# power_supply.net
KiCad netlist of a schematic drawn in Altium Designer
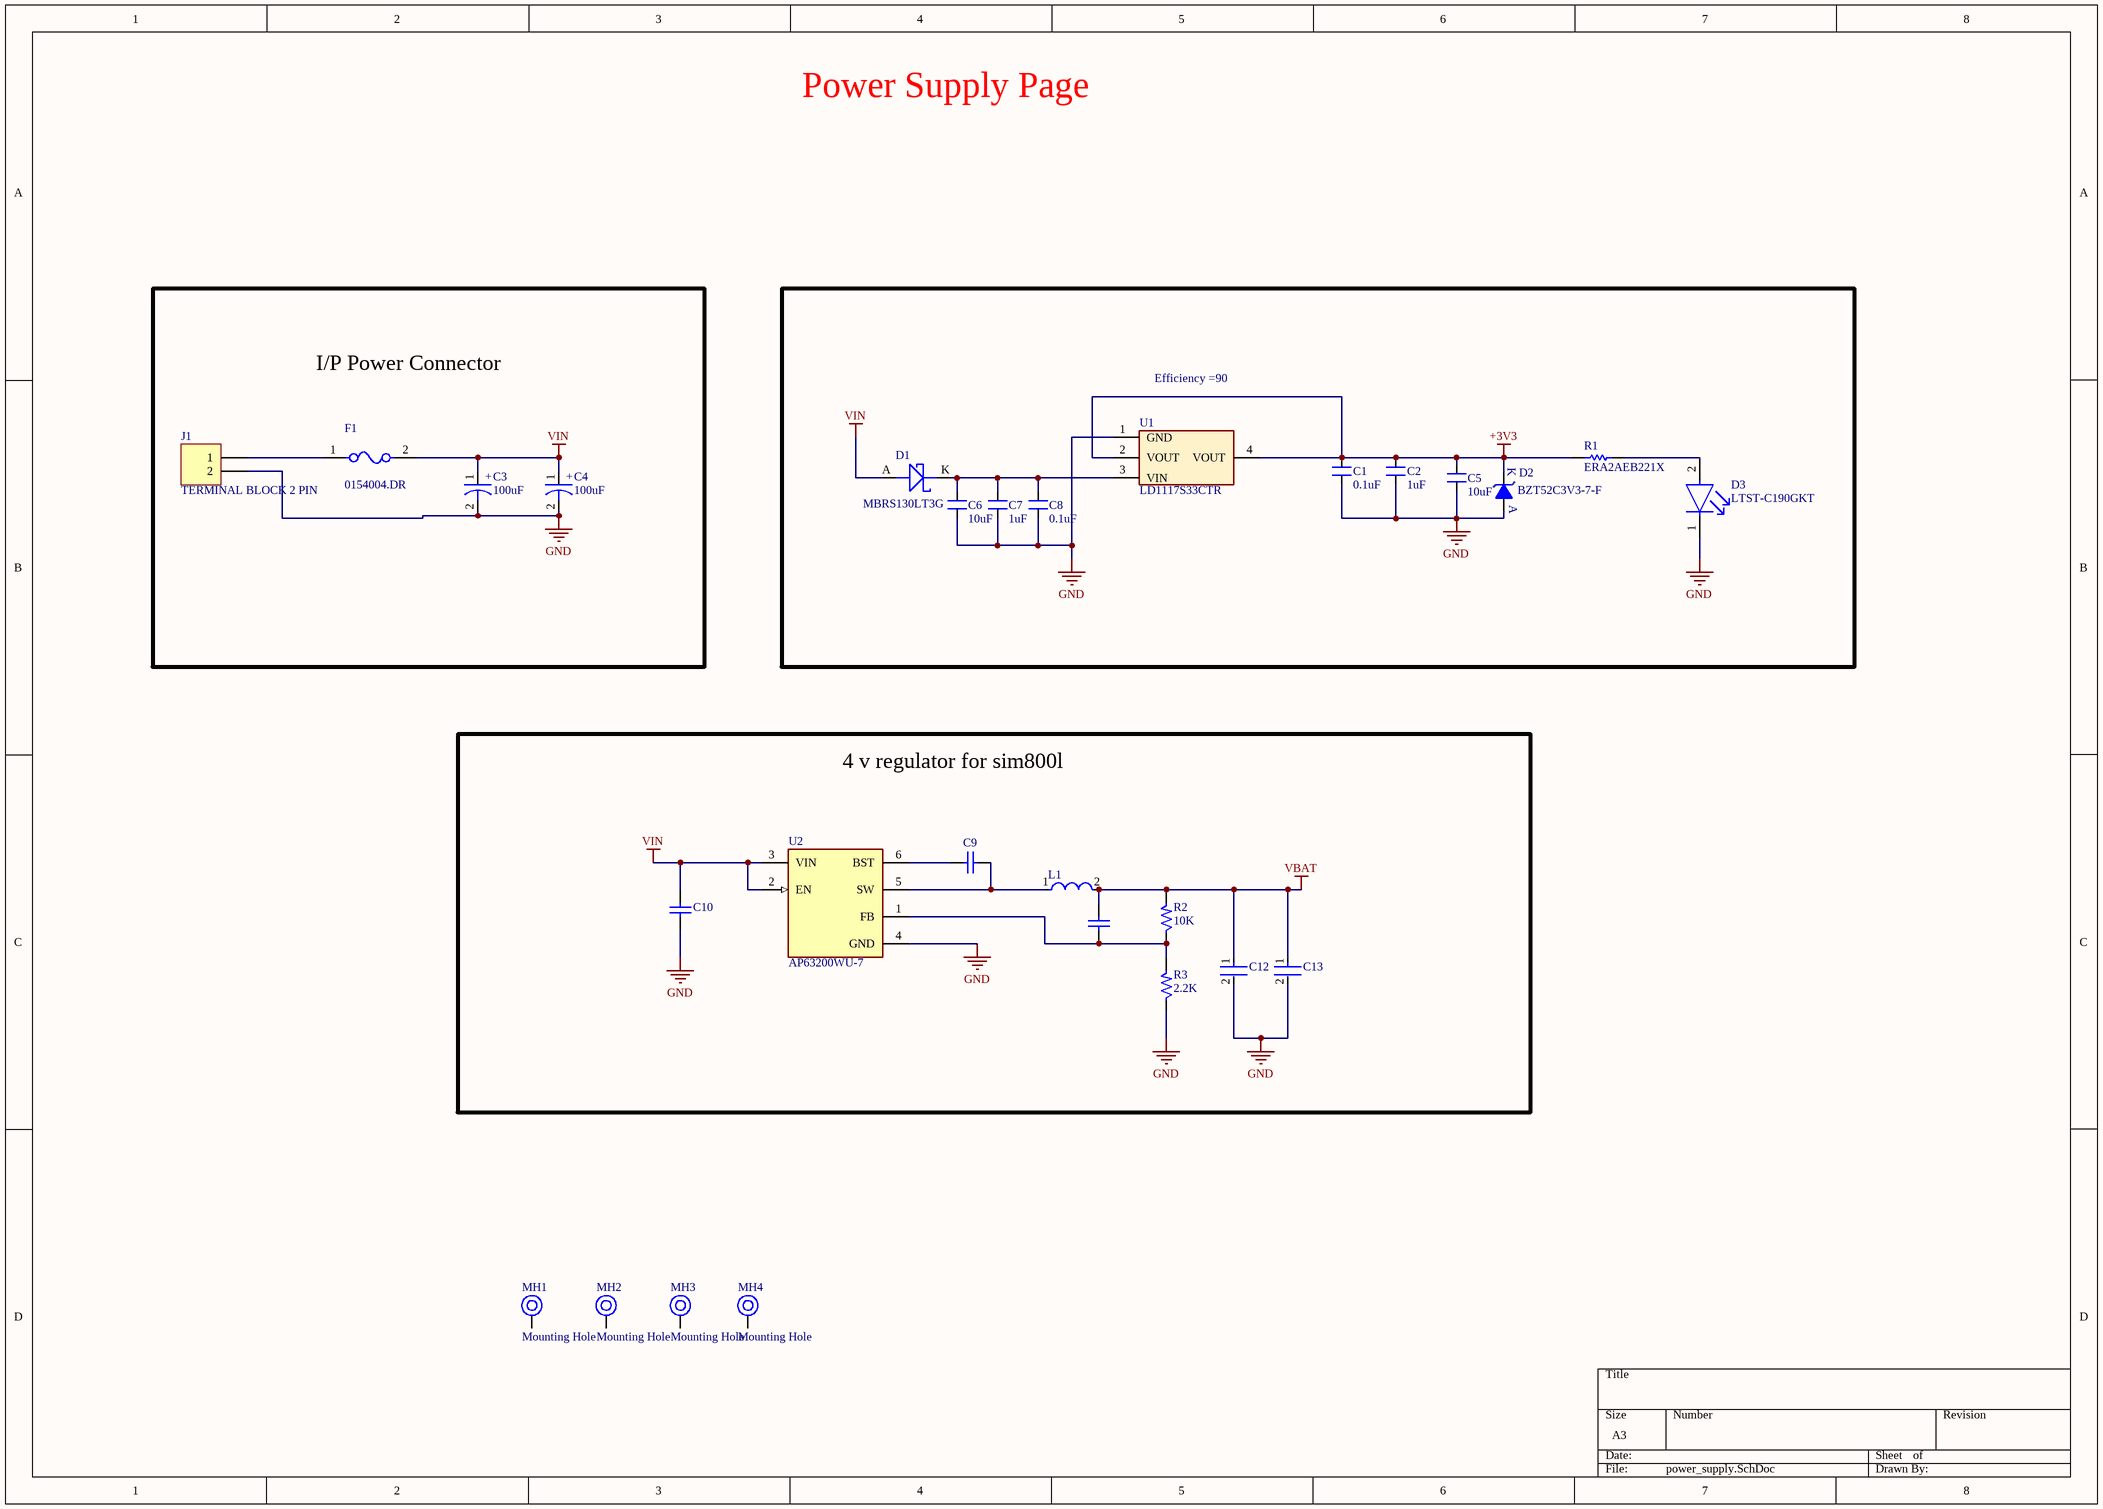
[diagram p0: power_supply.SchDoc]

(export (version "E")
  (design (tool "Eeschema 10.0.6"))
  (components
    (comp (ref "C1")
      (value "0.1uF")
      (footprint "CAP_0805")
      (description "0.1µF ±10% 50V Ceramic Capacitor X7R 0805 (2012 Metric)")
      (fields
        (field (name "MANUFACTURER") "Samsung")
        (field (name "MANUFACTURER PART NUMBER") "CL21B104KBCNNNC")
      )
      (libsource (lib "ESTEEMPCBLIB") (part "CAP_0.1uF-50V-10%-0805"))
    )
    (comp (ref "C2")
      (value "1uF")
      (footprint "CAP_0805")
      (description "1µF ±5% 50V Ceramic Capacitor X7R 0805 (2012 Metric)")
      (fields
        (field (name "MANUFACTURER") "Samsung")
        (field (name "MANUFACTURER PART NUMBER") "CC0805JKX7R9BB105")
      )
      (libsource (lib "ESTEEMPCBLIB") (part "CAP_1uF-50V-5%-0805"))
    )
    (comp (ref "C3")
      (value "100uF")
      (footprint "ACAP_P305_D393_H393_RAD")
      (description "100µF 50V Aluminum Polymer Capacitor Radial, Can - SMD 28mOhm 4000 Hrs @ 125°C")
      (fields
        (field (name "MANUFACTURER") "Nichicon")
        (field (name "MANUFACTURER PART NUMBER") "GYA1H101MCQ1GS")
      )
      (libsource (lib "ESTEEMPCBLIB") (part "CAP-P_100uF-50V-20%-RAD"))
    )
    (comp (ref "C4")
      (value "100uF")
      (footprint "ACAP_P305_D393_H393_RAD")
      (description "100µF 50V Aluminum Polymer Capacitor Radial, Can - SMD 28mOhm 4000 Hrs @ 125°C")
      (fields
        (field (name "MANUFACTURER") "Nichicon")
        (field (name "MANUFACTURER PART NUMBER") "GYA1H101MCQ1GS")
      )
      (libsource (lib "ESTEEMPCBLIB") (part "CAP-P_100uF-50V-20%-RAD"))
    )
    (comp (ref "C5")
      (value "10uF")
      (footprint "CAP_1206")
      (description "10µF ±10% 50V Ceramic Capacitor X7R 1206 (3216 Metric)")
      (fields
        (field (name "MANUFACTURER") "KEMET")
        (field (name "MANUFACTURER PART NUMBER") "CL31B106KBHNNNE")
      )
      (libsource (lib "ESTEEMPCBLIB") (part "CAP_10uF-50V-10%-1206"))
    )
    (comp (ref "C6")
      (value "10uF")
      (footprint "CAP_1206")
      (description "10µF ±10% 50V Ceramic Capacitor X7R 1206 (3216 Metric)")
      (fields
        (field (name "MANUFACTURER") "KEMET")
        (field (name "MANUFACTURER PART NUMBER") "CL31B106KBHNNNE")
      )
      (libsource (lib "ESTEEMPCBLIB") (part "CAP_10uF-50V-10%-1206"))
    )
    (comp (ref "C7")
      (value "1uF")
      (footprint "CAP_0805")
      (description "1µF ±5% 50V Ceramic Capacitor X7R 0805 (2012 Metric)")
      (fields
        (field (name "MANUFACTURER") "Samsung")
        (field (name "MANUFACTURER PART NUMBER") "CC0805JKX7R9BB105")
      )
      (libsource (lib "ESTEEMPCBLIB") (part "CAP_1uF-50V-5%-0805"))
    )
    (comp (ref "C8")
      (value "0.1uF")
      (footprint "CAP_0805")
      (description "0.1µF ±10% 50V Ceramic Capacitor X7R 0805 (2012 Metric)")
      (fields
        (field (name "MANUFACTURER") "Samsung")
        (field (name "MANUFACTURER PART NUMBER") "CL21B104KBCNNNC")
      )
      (libsource (lib "ESTEEMPCBLIB") (part "CAP_0.1uF-50V-10%-0805"))
    )
    (comp (ref "C9")
      (value "04026D104KAT2A")
      (footprint "CAPC1005X56X25LL10T15")
      (fields (field (name "MANUFACTURER") "AVX Interconnect / Elco"))
      (libsource (lib "Altium Content Vault") (part "CAP"))
    )
    (comp (ref "C10")
      (value "AMK105CBJ106MV-F")
      (footprint "CAPC0402(1005)60_N")
      (description "None")
      (fields (field (name "TOLERANCE") "20%"))
      (libsource (lib "Altium Content Vault") (part "CAP"))
    )
    (comp (ref "C11")
      (value "GRM1555C1H101JA01D")
      (footprint "CAPC1005X55X25ML05T10")
      (fields (field (name "MANUFACTURER") "Murata"))
      (libsource (lib "Altium Content Vault") (part "CAP"))
    )
    (comp (ref "C12")
      (value "GRM21BR60J226ME39L")
      (footprint "FP-GRM21B-0_15-IPC_B")
      (description "Chip Multilayer Ceramic Capacitors for General Purpose, 0805, 22uF, X5R, 15%, 20%, 6.3V")
      (fields (field (name "VOLTAGE") "6.3V") (field (name "TOLERANCE") "20%"))
      (libsource (lib "Altium Content Vault") (part "b4654b650e69147ec39a6b967a45e02"))
    )
    (comp (ref "C13")
      (value "GRM21BR60J226ME39L")
      (footprint "FP-GRM21B-0_15-IPC_B")
      (description "Chip Multilayer Ceramic Capacitors for General Purpose, 0805, 22uF, X5R, 15%, 20%, 6.3V")
      (fields (field (name "VOLTAGE") "6.3V") (field (name "TOLERANCE") "20%"))
      (libsource (lib "Altium Content Vault") (part "b4654b650e69147ec39a6b967a45e02"))
    )
    (comp (ref "D1")
      (value "MBRS130LT3G")
      (footprint "DIO_SMB_DO-214AA")
      (description "Diode Schottky 30V 2A Surface Mount SMB")
      (fields (field (name "MANUFACTURER") "ON Semiconductor"))
      (libsource (lib "ESTEEMPCBLIB") (part "DIO-S_445mV-30V-2A-SMB"))
    )
    (comp (ref "D2")
      (value "BZT52C3V3-7-F")
      (footprint "DIO_SOD-123")
      (description "Zener Diode 3.3V 500mW ±6% Surface Mount SOD-123")
      (fields (field (name "MANUFACTURER") "Diodes Incorporated"))
      (libsource (lib "ESTEEMPCBLIB") (part "DIO-Z_3.3V-500mW-SOD123"))
    )
    (comp (ref "D3")
      (value "LTST-C190GKT")
      (footprint "FP-LTST-C190GKT-MFG")
      (description "LED GREEN CLEAR CHIP SMD")
      (fields (field (name "VOLTAGE") "2V"))
      (libsource (lib "Altium Content Vault") (part "8706943c75ba83719d021d2fdc84c58"))
    )
    (comp (ref "F1")
      (value "0154004.DR")
      (footprint "FP-0154-MFG")
      (description "FUSE BRD MNT 4A 125VAC/VDC 2SMD")
      (fields
        (field (name "MANUFACTURER") "Littelfuse")
        (field (name "OCTOPART") "https://octopart.com/0154004.dr-littelfuse-565861")
      )
      (libsource (lib "Altium Content Vault") (part "5bcf9b9f640e542cf0359d10258e979"))
    )
    (comp (ref "J1")
      (value "TERMINAL BLOCK 2 PIN")
      (footprint "CON2_P196_1729128_TH_ST")
      (description "2 Pins, 1 Row 5mm Pitch, straight Connector, male")
      (fields
        (field (name "MANUFACTURER") "Phoenix Contact")
        (field (name "MANUFACTURER PART NUMBER") "MKDSN1,5/2")
      )
      (libsource (lib "ESTEEMPCBLIB") (part "CON-TB_2X1-196-ST-TH"))
    )
    (comp (ref "L1")
      (value "MLZ1005M2R2WT000")
      (footprint "FP-MLZ1005-IPC_B")
      (description "Shielded Multilayer Inductor 2.2uH ±20% 350mA 715mΩ SMD 0402")
      (fields (field (name "TOLERANCE") "20%"))
      (libsource (lib "Altium Content Vault") (part "725321dda6339637d4d059423bc1c3c"))
    )
    (comp (ref "MH1")
      (value "Mounting Hole")
      (footprint "MOUNTING")
      (fields (field (name "MANUFACTURER PART NUMBER") "NA"))
      (libsource (lib "ESTEEMPCBLIB") (part "MH_3.5H_6D"))
    )
    (comp (ref "MH2")
      (value "Mounting Hole")
      (footprint "MOUNTING")
      (fields (field (name "MANUFACTURER PART NUMBER") "NA"))
      (libsource (lib "ESTEEMPCBLIB") (part "MH_3.5H_6D"))
    )
    (comp (ref "MH3")
      (value "Mounting Hole")
      (footprint "MOUNTING")
      (fields (field (name "MANUFACTURER PART NUMBER") "NA"))
      (libsource (lib "ESTEEMPCBLIB") (part "MH_3.5H_6D"))
    )
    (comp (ref "MH4")
      (value "Mounting Hole")
      (footprint "MOUNTING")
      (fields (field (name "MANUFACTURER PART NUMBER") "NA"))
      (libsource (lib "ESTEEMPCBLIB") (part "MH_3.5H_6D"))
    )
    (comp (ref "R1")
      (value "ERA2AEB221X")
      (footprint "RESC1005X40X25LL10T10")
      (fields (field (name "MANUFACTURER") "Panasonic"))
      (libsource (lib "Altium Content Vault") (part "RES"))
    )
    (comp (ref "R2")
      (value "10K")
      (footprint "RES_0603")
      (description "10 kOhms ±1% 0.1W, 1/10W Chip Resistor 0603 (1608 Metric) Automotive AEC-Q200 Thick Film")
      (fields (field (name "MANUFACTURER") "Walsin") (field (name "MANUFACTURER PART NUMBER") "WR06X1002FTL"))
      (libsource (lib "ESTEEMPCBLIB") (part "RES_10K-0.1W-1%-0603"))
    )
    (comp (ref "R3")
      (value "2.2K")
      (footprint "RES_0805")
      (description "2.2 kOhms ±1% 0.125W, 1/8W Chip Resistor 0805 (2012 Metric) Thick Film")
      (fields
        (field (name "MANUFACTURER") "Stackpole Electronics")
        (field (name "MANUFACTURER PART NUMBER") "CRG0805F2K2")
      )
      (libsource (lib "ESTEEMPCBLIB") (part "RES_2.2K-0.125W-1%-0805"))
    )
    (comp (ref "U1")
      (value "LD1117S33CTR")
      (footprint "SOT223_3")
      (description "Linear Voltage Regulator IC 1 Output 800mA SOT-223")
      (fields (field (name "MANUFACTURER") "STMicroelectronics"))
      (libsource (lib "ESTEEMPCBLIB") (part "REG_15V-3.3V-0.9A-12W-SOT223"))
    )
    (comp (ref "U2")
      (value "AP63200WU-7")
      (footprint "FP-TSOT26-MFG")
      (description "IC REG BUCK ADJUSTABLE 2A TSOT26")
      (fields
        (field (name "OCTOPART") "https://octopart.com/ap63200wu-7-diodes+inc.-98099548")
        (field (name "MANUFACTURER") "Diodes Inc.")
      )
      (libsource (lib "Altium Content Vault") (part "2ae3aed49e7ee94ca813948749813a1"))
    )
  )
  (nets
    (net (code "1") (name "+3V3") (class "Default")
      (node (ref "C1") (pin "2") (pinfunction "2_2") (pintype "passive"))
      (node (ref "C2") (pin "2") (pinfunction "2_2") (pintype "passive"))
      (node (ref "C5") (pin "2") (pinfunction "2_2") (pintype "passive"))
      (node (ref "D2") (pin "K") (pinfunction "K_K") (pintype "passive"))
      (node (ref "R1") (pin "1") (pinfunction "1_1") (pintype "passive"))
      (node (ref "U1") (pin "2") (pinfunction "VOUT_2") (pintype "passive"))
      (node (ref "U1") (pin "4") (pinfunction "VOUT_4") (pintype "passive"))
    )
    (net (code "2") (name "GND") (class "Default")
      (node (ref "C1") (pin "1") (pinfunction "1_1") (pintype "passive"))
      (node (ref "C10") (pin "1") (pinfunction "1_1") (pintype "passive"))
      (node (ref "C12") (pin "2") (pinfunction "2_2") (pintype "passive"))
      (node (ref "C13") (pin "2") (pinfunction "2_2") (pintype "passive"))
      (node (ref "C2") (pin "1") (pinfunction "1_1") (pintype "passive"))
      (node (ref "C3") (pin "2") (pinfunction "2_2") (pintype "passive"))
      (node (ref "C4") (pin "2") (pinfunction "2_2") (pintype "passive"))
      (node (ref "C5") (pin "1") (pinfunction "1_1") (pintype "passive"))
      (node (ref "C6") (pin "1") (pinfunction "1_1") (pintype "passive"))
      (node (ref "C7") (pin "1") (pinfunction "1_1") (pintype "passive"))
      (node (ref "C8") (pin "1") (pinfunction "1_1") (pintype "passive"))
      (node (ref "D2") (pin "A") (pinfunction "A_A") (pintype "passive"))
      (node (ref "D3") (pin "1") (pinfunction "C_1") (pintype "passive"))
      (node (ref "J1") (pin "2") (pinfunction "2_2") (pintype "passive"))
      (node (ref "R3") (pin "1") (pinfunction "1_1") (pintype "passive"))
      (node (ref "U1") (pin "1") (pinfunction "GND_1") (pintype "passive"))
      (node (ref "U2") (pin "4") (pinfunction "GND_4") (pintype "power_in"))
    )
    (net (code "3") (name "Net-(D3-A)") (class "Default")
      (node (ref "D3") (pin "2") (pinfunction "A_2") (pintype "passive"))
      (node (ref "R1") (pin "2") (pinfunction "2_2") (pintype "passive"))
    )
    (net (code "4") (name "Net-(F1-Pad1)") (class "Default")
      (node (ref "F1") (pin "1") (pinfunction "1_1") (pintype "passive"))
      (node (ref "J1") (pin "1") (pinfunction "1_1") (pintype "passive"))
    )
    (net (code "5") (name "Net-(U1-VIN)") (class "Default")
      (node (ref "C6") (pin "2") (pinfunction "2_2") (pintype "passive"))
      (node (ref "C7") (pin "2") (pinfunction "2_2") (pintype "passive"))
      (node (ref "C8") (pin "2") (pinfunction "2_2") (pintype "passive"))
      (node (ref "D1") (pin "K") (pinfunction "K_K") (pintype "passive"))
      (node (ref "U1") (pin "3") (pinfunction "VIN_3") (pintype "passive"))
    )
    (net (code "6") (name "Net-(U2-BST)") (class "Default")
      (node (ref "C9") (pin "1") (pinfunction "1_1") (pintype "passive"))
      (node (ref "U2") (pin "6") (pinfunction "BST_6") (pintype "passive"))
    )
    (net (code "7") (name "Net-(U2-FB)") (class "Default")
      (node (ref "C11") (pin "1") (pinfunction "1_1") (pintype "passive"))
      (node (ref "R2") (pin "1") (pinfunction "1_1") (pintype "passive"))
      (node (ref "R3") (pin "2") (pinfunction "2_2") (pintype "passive"))
      (node (ref "U2") (pin "1") (pinfunction "FB_1") (pintype "passive"))
    )
    (net (code "8") (name "Net-(U2-SW)") (class "Default")
      (node (ref "C9") (pin "2") (pinfunction "2_2") (pintype "passive"))
      (node (ref "L1") (pin "1") (pinfunction "1_1") (pintype "passive"))
      (node (ref "U2") (pin "5") (pinfunction "SW_5") (pintype "passive"))
    )
    (net (code "9") (name "VBAT") (class "Default")
      (node (ref "C11") (pin "2") (pinfunction "2_2") (pintype "passive"))
      (node (ref "C12") (pin "1") (pinfunction "1_1") (pintype "passive"))
      (node (ref "C13") (pin "1") (pinfunction "1_1") (pintype "passive"))
      (node (ref "L1") (pin "2") (pinfunction "2_2") (pintype "passive"))
      (node (ref "R2") (pin "2") (pinfunction "2_2") (pintype "passive"))
    )
    (net (code "10") (name "VIN") (class "Default")
      (node (ref "C10") (pin "2") (pinfunction "2_2") (pintype "passive"))
      (node (ref "C3") (pin "1") (pinfunction "1_1") (pintype "passive"))
      (node (ref "C4") (pin "1") (pinfunction "1_1") (pintype "passive"))
      (node (ref "D1") (pin "A") (pinfunction "A_A") (pintype "passive"))
      (node (ref "F1") (pin "2") (pinfunction "2_2") (pintype "passive"))
      (node (ref "U2") (pin "2") (pinfunction "EN_2") (pintype "input"))
      (node (ref "U2") (pin "3") (pinfunction "VIN_3") (pintype "power_in"))
    )
    (net (code "11") (name "unconnected-(MH1-Pad1)") (class "Default")
      (node (ref "MH1") (pin "1") (pinfunction "1_1") (pintype "passive"))
    )
    (net (code "12") (name "unconnected-(MH2-Pad1)") (class "Default")
      (node (ref "MH2") (pin "1") (pinfunction "1_1") (pintype "passive"))
    )
    (net (code "13") (name "unconnected-(MH3-Pad1)") (class "Default")
      (node (ref "MH3") (pin "1") (pinfunction "1_1") (pintype "passive"))
    )
    (net (code "14") (name "unconnected-(MH4-Pad1)") (class "Default")
      (node (ref "MH4") (pin "1") (pinfunction "1_1") (pintype "passive"))
    )
  )
)
